# Decoder.net
KiCad netlist of a schematic drawn in Altium Designer
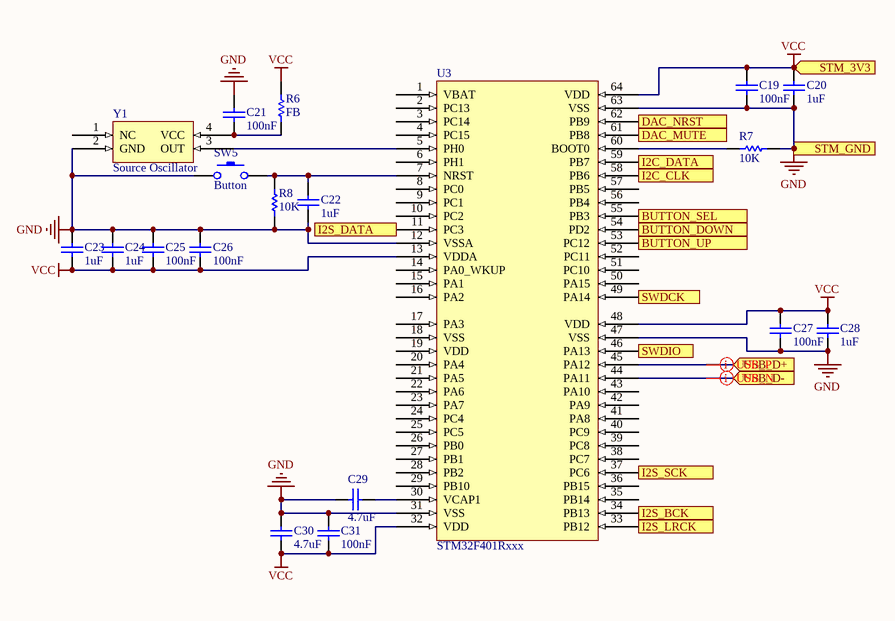
[diagram p0: Decoder.SchDoc]

(export (version "E")
  (design (tool "Eeschema 10.0.6"))
  (components
    (comp (ref "C19") (value "100nF") (footprint "SMC_0402") (libsource (lib "Common") (part "Cap Ceramic")))
    (comp (ref "C20") (value "1uF") (footprint "SMC_0402") (libsource (lib "Common") (part "Cap Ceramic")))
    (comp (ref "C21") (value "100nF") (footprint "SMC_0402") (libsource (lib "Common") (part "Cap Ceramic")))
    (comp (ref "C22") (value "1uF") (footprint "SMC_0402") (libsource (lib "Common") (part "Cap Ceramic")))
    (comp (ref "C23") (value "1uF") (footprint "SMC_0402") (libsource (lib "Common") (part "Cap Ceramic")))
    (comp (ref "C24") (value "1uF") (footprint "SMC_0402") (libsource (lib "Common") (part "Cap Ceramic")))
    (comp (ref "C25") (value "100nF") (footprint "SMC_0402") (libsource (lib "Common") (part "Cap Ceramic")))
    (comp (ref "C26") (value "100nF") (footprint "SMC_0402") (libsource (lib "Common") (part "Cap Ceramic")))
    (comp (ref "C27") (value "100nF") (footprint "SMC_0402") (libsource (lib "Common") (part "Cap Ceramic")))
    (comp (ref "C28") (value "1uF") (footprint "SMC_0402") (libsource (lib "Common") (part "Cap Ceramic")))
    (comp (ref "C29") (value "4.7uF") (footprint "SMC_0402") (libsource (lib "Common") (part "Cap Ceramic")))
    (comp (ref "C30") (value "4.7uF") (footprint "SMC_0402") (libsource (lib "Common") (part "Cap Ceramic")))
    (comp (ref "C31") (value "100nF") (footprint "SMC_0402") (libsource (lib "Common") (part "Cap Ceramic")))
    (comp (ref "R6") (value "FB") (footprint "SMR_0603") (libsource (lib "Common") (part "Res SMT")))
    (comp (ref "R7") (value "10K") (footprint "SMR_0402") (libsource (lib "Common") (part "Res SMT")))
    (comp (ref "R8") (value "10K") (footprint "SMR_0402") (libsource (lib "Common") (part "Res SMT")))
    (comp (ref "SW5") (value "Button") (footprint "Button") (libsource (lib "Button_Switch") (part "Button")))
    (comp (ref "U3")
      (value "STM32F401Rxxx")
      (footprint "TSQFP50P1200X1200X160-64N")
      (libsource (lib "Microcontroller") (part "STM32F401Rxxx"))
    )
    (comp (ref "Y1")
      (value "Source Oscillator")
      (footprint "SMD_3225")
      (libsource (lib "Oscillator") (part "Source Oscillator"))
    )
  )
  (nets
    (net (code "1") (name "/BUTTON_DOWN") (class "Default")
      (node (ref "U3") (pin "54") (pinfunction "PD2_54") (pintype "input"))
    )
    (net (code "2") (name "/BUTTON_SEL") (class "Default")
      (node (ref "U3") (pin "55") (pinfunction "PB3_55") (pintype "input"))
    )
    (net (code "3") (name "/BUTTON_UP") (class "Default")
      (node (ref "U3") (pin "53") (pinfunction "PC12_53") (pintype "input"))
    )
    (net (code "4") (name "/DAC_MUTE") (class "Default")
      (node (ref "U3") (pin "61") (pinfunction "PB8_61") (pintype "input"))
    )
    (net (code "5") (name "/DAC_NRST") (class "Default")
      (node (ref "U3") (pin "62") (pinfunction "PB9_62") (pintype "input"))
    )
    (net (code "6") (name "/I2C_CLK") (class "Default")
      (node (ref "U3") (pin "58") (pinfunction "PB6_58") (pintype "input"))
    )
    (net (code "7") (name "/I2C_DATA") (class "Default")
      (node (ref "U3") (pin "59") (pinfunction "PB7_59") (pintype "input"))
    )
    (net (code "8") (name "/I2S_BCK") (class "Default")
      (node (ref "U3") (pin "34") (pinfunction "PB13_34") (pintype "input"))
    )
    (net (code "9") (name "/I2S_DATA") (class "Default")
      (node (ref "U3") (pin "11") (pinfunction "PC3_11") (pintype "input"))
    )
    (net (code "10") (name "/I2S_LRCK") (class "Default")
      (node (ref "U3") (pin "33") (pinfunction "PB12_33") (pintype "input"))
    )
    (net (code "11") (name "/I2S_SCK") (class "Default")
      (node (ref "U3") (pin "37") (pinfunction "PC6_37") (pintype "input"))
    )
    (net (code "12") (name "/SWDCK") (class "Default")
      (node (ref "U3") (pin "49") (pinfunction "PA14_49") (pintype "input"))
    )
    (net (code "13") (name "/SWDIO") (class "Default")
      (node (ref "U3") (pin "46") (pinfunction "PA13_46") (pintype "input"))
    )
    (net (code "14") (name "/USB_D+") (class "Default")
      (node (ref "U3") (pin "45") (pinfunction "PA12_45") (pintype "input"))
    )
    (net (code "15") (name "/USB_D-") (class "Default")
      (node (ref "U3") (pin "44") (pinfunction "PA11_44") (pintype "input"))
    )
    (net (code "16") (name "GND") (class "Default")
      (node (ref "C19") (pin "1") (pinfunction "1_1") (pintype "passive"))
      (node (ref "C20") (pin "1") (pinfunction "1_1") (pintype "passive"))
      (node (ref "C21") (pin "2") (pinfunction "2_2") (pintype "passive"))
      (node (ref "C22") (pin "1") (pinfunction "1_1") (pintype "passive"))
      (node (ref "C23") (pin "2") (pinfunction "2_2") (pintype "passive"))
      (node (ref "C24") (pin "2") (pinfunction "2_2") (pintype "passive"))
      (node (ref "C25") (pin "2") (pinfunction "2_2") (pintype "passive"))
      (node (ref "C26") (pin "2") (pinfunction "2_2") (pintype "passive"))
      (node (ref "C27") (pin "1") (pinfunction "1_1") (pintype "passive"))
      (node (ref "C28") (pin "1") (pinfunction "1_1") (pintype "passive"))
      (node (ref "C29") (pin "1") (pinfunction "1_1") (pintype "passive"))
      (node (ref "C30") (pin "2") (pinfunction "2_2") (pintype "passive"))
      (node (ref "C31") (pin "2") (pinfunction "2_2") (pintype "passive"))
      (node (ref "R7") (pin "2") (pinfunction "2_2") (pintype "passive"))
      (node (ref "R8") (pin "2") (pinfunction "2_2") (pintype "passive"))
      (node (ref "SW5") (pin "1") (pinfunction "1_1") (pintype "passive"))
      (node (ref "U3") (pin "12") (pinfunction "VSSA_12") (pintype "input"))
      (node (ref "U3") (pin "31") (pinfunction "VSS_31") (pintype "input"))
      (node (ref "U3") (pin "47") (pinfunction "VSS_47") (pintype "input"))
      (node (ref "U3") (pin "63") (pinfunction "VSS_63") (pintype "input"))
      (node (ref "Y1") (pin "2") (pinfunction "GND_2") (pintype "input"))
    )
    (net (code "17") (name "Net-(U3-BOOT0)") (class "Default")
      (node (ref "R7") (pin "1") (pinfunction "1_1") (pintype "passive"))
      (node (ref "U3") (pin "60") (pinfunction "BOOT0_60") (pintype "input"))
    )
    (net (code "18") (name "Net-(U3-NRST)") (class "Default")
      (node (ref "C22") (pin "2") (pinfunction "2_2") (pintype "passive"))
      (node (ref "R8") (pin "1") (pinfunction "1_1") (pintype "passive"))
      (node (ref "SW5") (pin "2") (pinfunction "2_2") (pintype "passive"))
      (node (ref "U3") (pin "7") (pinfunction "NRST_7") (pintype "input"))
    )
    (net (code "19") (name "Net-(U3-PH0)") (class "Default")
      (node (ref "U3") (pin "5") (pinfunction "PH0_5") (pintype "input"))
      (node (ref "Y1") (pin "3") (pinfunction "OUT_3") (pintype "input"))
    )
    (net (code "20") (name "Net-(U3-VCAP1)") (class "Default")
      (node (ref "C29") (pin "2") (pinfunction "2_2") (pintype "passive"))
      (node (ref "U3") (pin "30") (pinfunction "VCAP1_30") (pintype "input"))
    )
    (net (code "21") (name "Net-(Y1-VCC)") (class "Default")
      (node (ref "C21") (pin "1") (pinfunction "1_1") (pintype "passive"))
      (node (ref "R6") (pin "1") (pinfunction "1_1") (pintype "passive"))
      (node (ref "Y1") (pin "4") (pinfunction "VCC_4") (pintype "input"))
    )
    (net (code "22") (name "VCC") (class "Default")
      (node (ref "C19") (pin "2") (pinfunction "2_2") (pintype "passive"))
      (node (ref "C20") (pin "2") (pinfunction "2_2") (pintype "passive"))
      (node (ref "C23") (pin "1") (pinfunction "1_1") (pintype "passive"))
      (node (ref "C24") (pin "1") (pinfunction "1_1") (pintype "passive"))
      (node (ref "C25") (pin "1") (pinfunction "1_1") (pintype "passive"))
      (node (ref "C26") (pin "1") (pinfunction "1_1") (pintype "passive"))
      (node (ref "C27") (pin "2") (pinfunction "2_2") (pintype "passive"))
      (node (ref "C28") (pin "2") (pinfunction "2_2") (pintype "passive"))
      (node (ref "C30") (pin "1") (pinfunction "1_1") (pintype "passive"))
      (node (ref "C31") (pin "1") (pinfunction "1_1") (pintype "passive"))
      (node (ref "R6") (pin "2") (pinfunction "2_2") (pintype "passive"))
      (node (ref "U3") (pin "13") (pinfunction "VDDA_13") (pintype "input"))
      (node (ref "U3") (pin "32") (pinfunction "VDD_32") (pintype "input"))
      (node (ref "U3") (pin "48") (pinfunction "VDD_48") (pintype "input"))
      (node (ref "U3") (pin "64") (pinfunction "VDD_64") (pintype "input"))
    )
    (net (code "23") (name "unconnected-(U3-PA0_WKUP-Pad14)") (class "Default")
      (node (ref "U3") (pin "14") (pinfunction "PA0_WKUP_14") (pintype "input"))
    )
    (net (code "24") (name "unconnected-(U3-PA1-Pad15)") (class "Default")
      (node (ref "U3") (pin "15") (pinfunction "PA1_15") (pintype "input"))
    )
    (net (code "25") (name "unconnected-(U3-PA2-Pad16)") (class "Default")
      (node (ref "U3") (pin "16") (pinfunction "PA2_16") (pintype "input"))
    )
    (net (code "26") (name "unconnected-(U3-PA3-Pad17)") (class "Default")
      (node (ref "U3") (pin "17") (pinfunction "PA3_17") (pintype "input"))
    )
    (net (code "27") (name "unconnected-(U3-PA4-Pad20)") (class "Default")
      (node (ref "U3") (pin "20") (pinfunction "PA4_20") (pintype "input"))
    )
    (net (code "28") (name "unconnected-(U3-PA5-Pad21)") (class "Default")
      (node (ref "U3") (pin "21") (pinfunction "PA5_21") (pintype "input"))
    )
    (net (code "29") (name "unconnected-(U3-PA6-Pad22)") (class "Default")
      (node (ref "U3") (pin "22") (pinfunction "PA6_22") (pintype "input"))
    )
    (net (code "30") (name "unconnected-(U3-PA7-Pad23)") (class "Default")
      (node (ref "U3") (pin "23") (pinfunction "PA7_23") (pintype "input"))
    )
    (net (code "31") (name "unconnected-(U3-PA8-Pad41)") (class "Default")
      (node (ref "U3") (pin "41") (pinfunction "PA8_41") (pintype "input"))
    )
    (net (code "32") (name "unconnected-(U3-PA9-Pad42)") (class "Default")
      (node (ref "U3") (pin "42") (pinfunction "PA9_42") (pintype "input"))
    )
    (net (code "33") (name "unconnected-(U3-PA10-Pad43)") (class "Default")
      (node (ref "U3") (pin "43") (pinfunction "PA10_43") (pintype "input"))
    )
    (net (code "34") (name "unconnected-(U3-PA15-Pad50)") (class "Default")
      (node (ref "U3") (pin "50") (pinfunction "PA15_50") (pintype "input"))
    )
    (net (code "35") (name "unconnected-(U3-PB0-Pad26)") (class "Default")
      (node (ref "U3") (pin "26") (pinfunction "PB0_26") (pintype "input"))
    )
    (net (code "36") (name "unconnected-(U3-PB1-Pad27)") (class "Default")
      (node (ref "U3") (pin "27") (pinfunction "PB1_27") (pintype "input"))
    )
    (net (code "37") (name "unconnected-(U3-PB2-Pad28)") (class "Default")
      (node (ref "U3") (pin "28") (pinfunction "PB2_28") (pintype "input"))
    )
    (net (code "38") (name "unconnected-(U3-PB4-Pad56)") (class "Default")
      (node (ref "U3") (pin "56") (pinfunction "PB4_56") (pintype "input"))
    )
    (net (code "39") (name "unconnected-(U3-PB5-Pad57)") (class "Default")
      (node (ref "U3") (pin "57") (pinfunction "PB5_57") (pintype "input"))
    )
    (net (code "40") (name "unconnected-(U3-PB10-Pad29)") (class "Default")
      (node (ref "U3") (pin "29") (pinfunction "PB10_29") (pintype "input"))
    )
    (net (code "41") (name "unconnected-(U3-PB14-Pad35)") (class "Default")
      (node (ref "U3") (pin "35") (pinfunction "PB14_35") (pintype "input"))
    )
    (net (code "42") (name "unconnected-(U3-PB15-Pad36)") (class "Default")
      (node (ref "U3") (pin "36") (pinfunction "PB15_36") (pintype "input"))
    )
    (net (code "43") (name "unconnected-(U3-PC0-Pad8)") (class "Default")
      (node (ref "U3") (pin "8") (pinfunction "PC0_8") (pintype "input"))
    )
    (net (code "44") (name "unconnected-(U3-PC1-Pad9)") (class "Default")
      (node (ref "U3") (pin "9") (pinfunction "PC1_9") (pintype "input"))
    )
    (net (code "45") (name "unconnected-(U3-PC2-Pad10)") (class "Default")
      (node (ref "U3") (pin "10") (pinfunction "PC2_10") (pintype "input"))
    )
    (net (code "46") (name "unconnected-(U3-PC4-Pad24)") (class "Default")
      (node (ref "U3") (pin "24") (pinfunction "PC4_24") (pintype "input"))
    )
    (net (code "47") (name "unconnected-(U3-PC5-Pad25)") (class "Default")
      (node (ref "U3") (pin "25") (pinfunction "PC5_25") (pintype "input"))
    )
    (net (code "48") (name "unconnected-(U3-PC7-Pad38)") (class "Default")
      (node (ref "U3") (pin "38") (pinfunction "PC7_38") (pintype "input"))
    )
    (net (code "49") (name "unconnected-(U3-PC8-Pad39)") (class "Default")
      (node (ref "U3") (pin "39") (pinfunction "PC8_39") (pintype "input"))
    )
    (net (code "50") (name "unconnected-(U3-PC9-Pad40)") (class "Default")
      (node (ref "U3") (pin "40") (pinfunction "PC9_40") (pintype "input"))
    )
    (net (code "51") (name "unconnected-(U3-PC10-Pad51)") (class "Default")
      (node (ref "U3") (pin "51") (pinfunction "PC10_51") (pintype "input"))
    )
    (net (code "52") (name "unconnected-(U3-PC11-Pad52)") (class "Default")
      (node (ref "U3") (pin "52") (pinfunction "PC11_52") (pintype "input"))
    )
    (net (code "53") (name "unconnected-(U3-PC13-Pad2)") (class "Default")
      (node (ref "U3") (pin "2") (pinfunction "PC13_2") (pintype "input"))
    )
    (net (code "54") (name "unconnected-(U3-PC14-Pad3)") (class "Default")
      (node (ref "U3") (pin "3") (pinfunction "PC14_3") (pintype "input"))
    )
    (net (code "55") (name "unconnected-(U3-PC15-Pad4)") (class "Default")
      (node (ref "U3") (pin "4") (pinfunction "PC15_4") (pintype "input"))
    )
    (net (code "56") (name "unconnected-(U3-PH1-Pad6)") (class "Default")
      (node (ref "U3") (pin "6") (pinfunction "PH1_6") (pintype "input"))
    )
    (net (code "57") (name "unconnected-(U3-VBAT-Pad1)") (class "Default")
      (node (ref "U3") (pin "1") (pinfunction "VBAT_1") (pintype "input"))
    )
    (net (code "58") (name "unconnected-(U3-VDD-Pad19)") (class "Default")
      (node (ref "U3") (pin "19") (pinfunction "VDD_19") (pintype "input"))
    )
    (net (code "59") (name "unconnected-(U3-VSS-Pad18)") (class "Default")
      (node (ref "U3") (pin "18") (pinfunction "VSS_18") (pintype "input"))
    )
    (net (code "60") (name "unconnected-(Y1-NC-Pad1)") (class "Default")
      (node (ref "Y1") (pin "1") (pinfunction "NC_1") (pintype "input"))
    )
  )
)
